# Power.net
KiCad netlist of a schematic drawn in Altium Designer
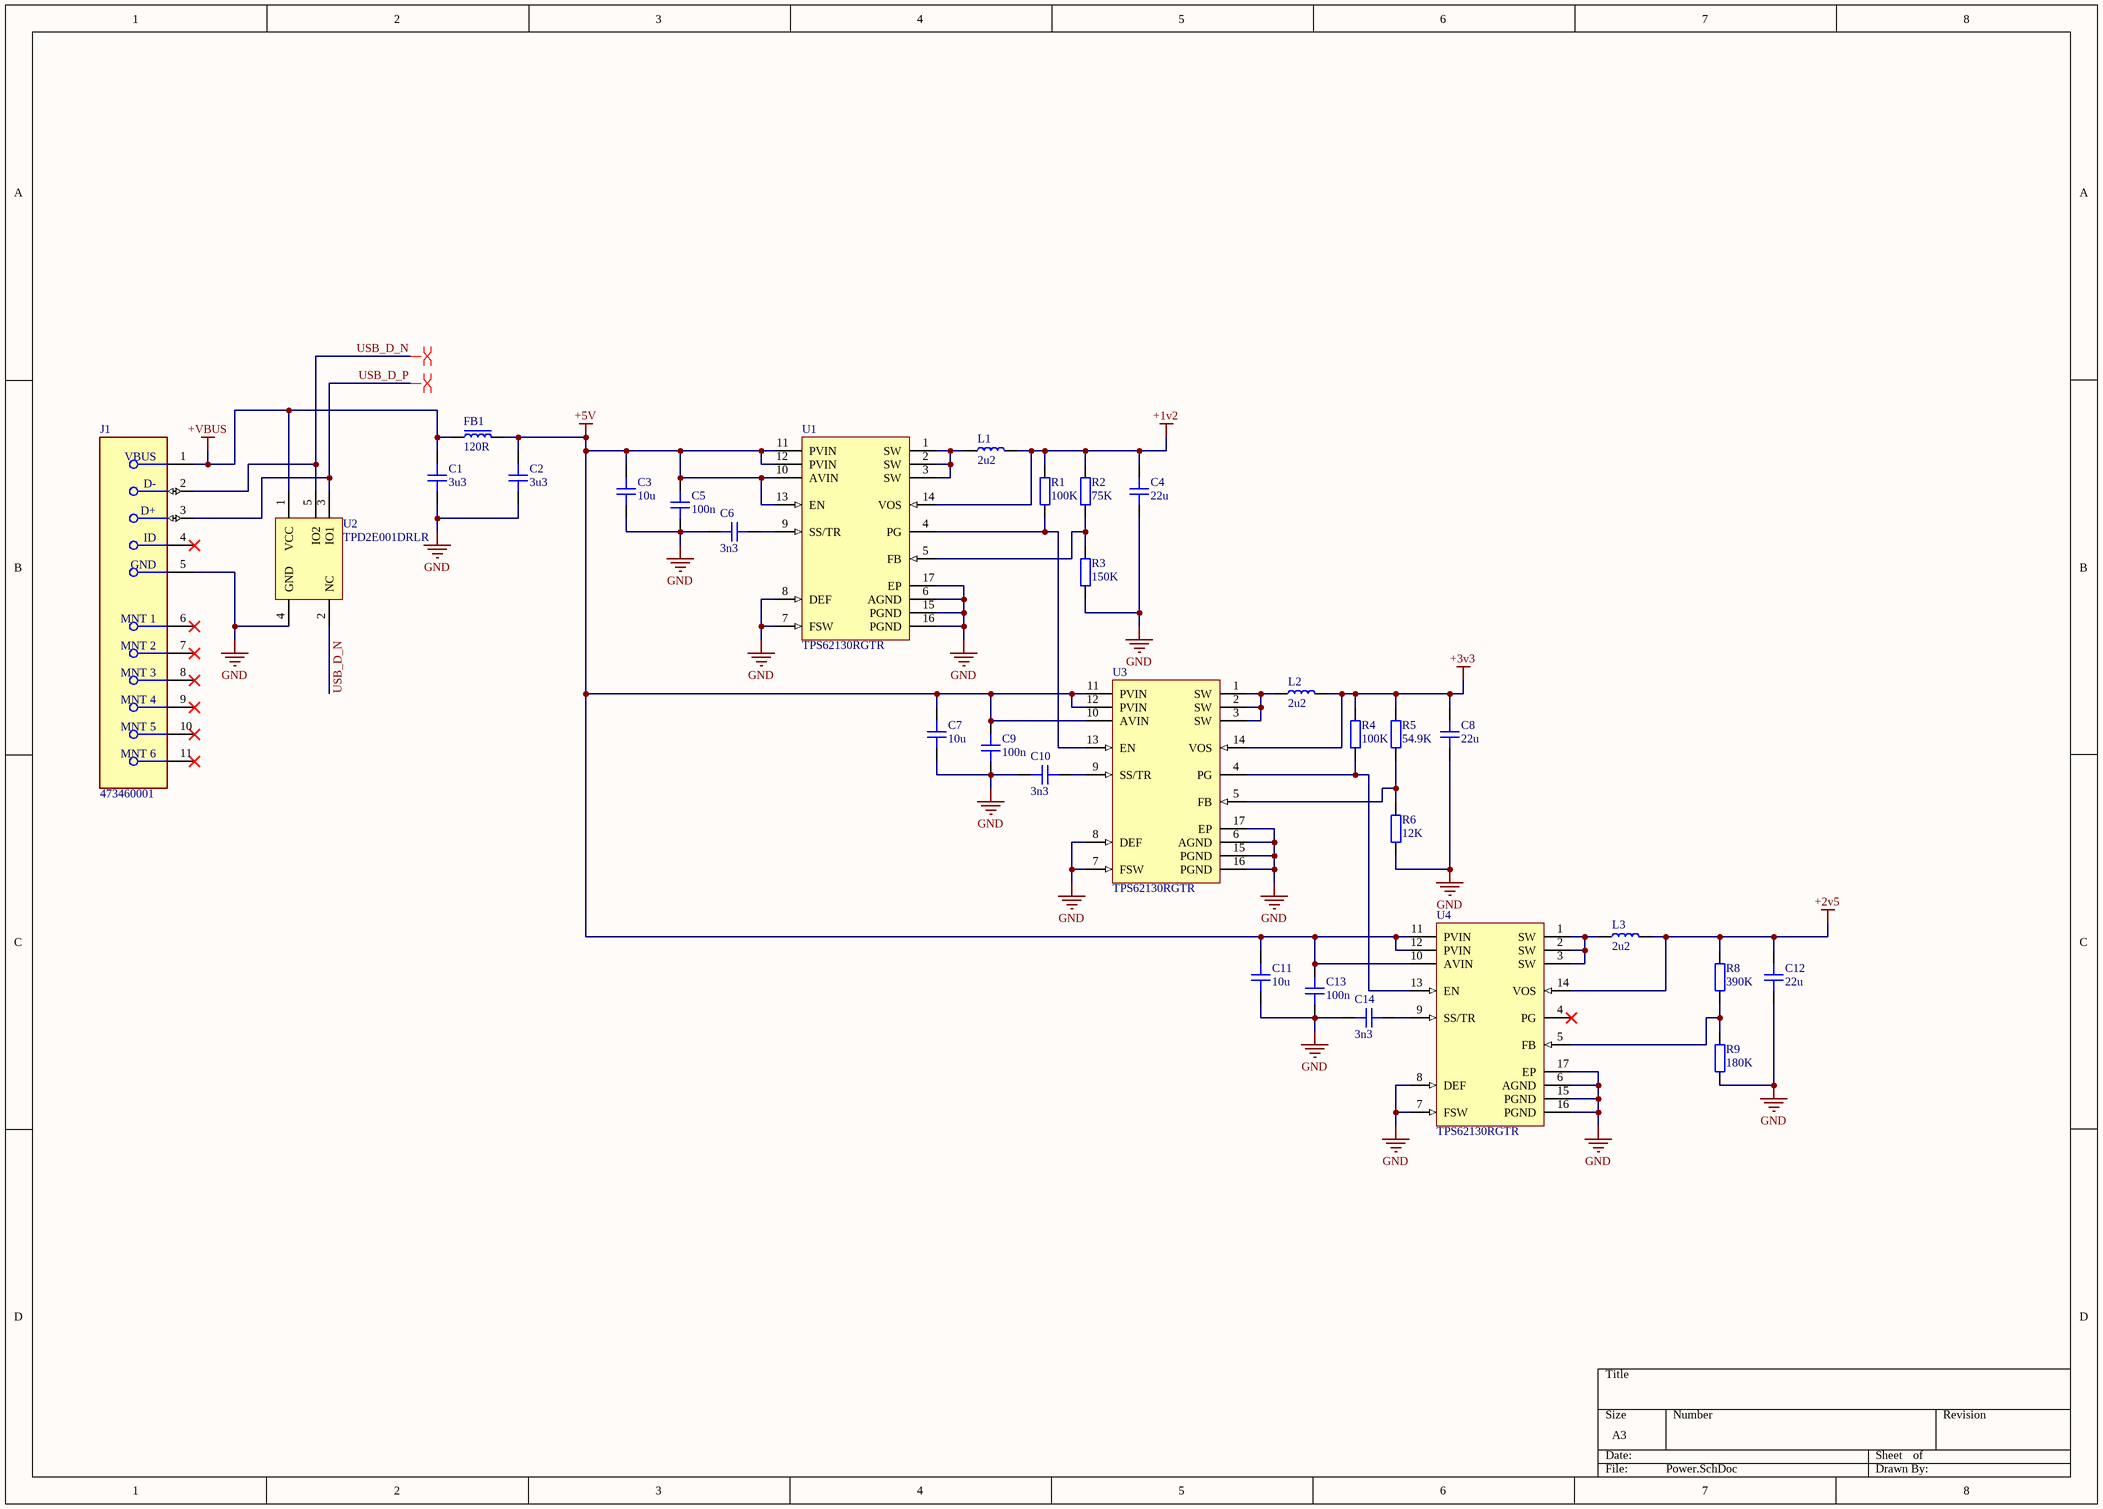
[diagram p0: Power.SchDoc]

(export (version "E")
  (design (tool "Eeschema 10.0.6"))
  (components
    (comp (ref "C1")
      (value "3u3")
      (footprint "CAP_0603")
      (description "Capacitor SMD 0603")
      (fields (field (name "MANUFACTURER PART NUMBER") "TCC0603X5R335M250CT"))
      (libsource (lib "Schematic-Lib-PhilsLab") (part "CAP_0603"))
    )
    (comp (ref "C2")
      (value "3u3")
      (footprint "CAP_0603")
      (description "Capacitor SMD 0603")
      (fields (field (name "MANUFACTURER PART NUMBER") "TCC0603X5R335M250CT"))
      (libsource (lib "Schematic-Lib-PhilsLab") (part "CAP_0603"))
    )
    (comp (ref "C3")
      (value "10u")
      (footprint "CAP_0805")
      (description "Capacitor SMD 0805")
      (fields (field (name "MANUFACTURER PART NUMBER") "CL21B106KOQNNNE"))
      (libsource (lib "Schematic-Lib-PhilsLab") (part "CAP_0805"))
    )
    (comp (ref "C4")
      (value "22u")
      (footprint "CAP_0805")
      (description "Capacitor SMD 0805")
      (fields (field (name "MANUFACTURER PART NUMBER") "GRM21BZ71A226ME15L"))
      (libsource (lib "Schematic-Lib-PhilsLab") (part "CAP_0805"))
    )
    (comp (ref "C5")
      (value "100n")
      (footprint "CAP_0402")
      (description "Capacitor SMD 0402")
      (fields (field (name "MANUFACTURER PART NUMBER") "CL05B104KO5NNNC"))
      (libsource (lib "Schematic-Lib-PhilsLab") (part "CAP_0402"))
    )
    (comp (ref "C6")
      (value "3n3")
      (footprint "CAP_0402")
      (description "Capacitor SMD 0402")
      (fields (field (name "MANUFACTURER PART NUMBER") "CL05B332KB5NNNC"))
      (libsource (lib "Schematic-Lib-PhilsLab") (part "CAP_0402"))
    )
    (comp (ref "C7")
      (value "10u")
      (footprint "CAP_0805")
      (description "Capacitor SMD 0805")
      (fields (field (name "MANUFACTURER PART NUMBER") "CL21B106KOQNNNE"))
      (libsource (lib "Schematic-Lib-PhilsLab") (part "CAP_0805"))
    )
    (comp (ref "C8")
      (value "22u")
      (footprint "CAP_0805")
      (description "Capacitor SMD 0805")
      (fields (field (name "MANUFACTURER PART NUMBER") "GRM21BZ71A226ME15L"))
      (libsource (lib "Schematic-Lib-PhilsLab") (part "CAP_0805"))
    )
    (comp (ref "C9")
      (value "100n")
      (footprint "CAP_0402")
      (description "Capacitor SMD 0402")
      (fields (field (name "MANUFACTURER PART NUMBER") "CL05B104KO5NNNC"))
      (libsource (lib "Schematic-Lib-PhilsLab") (part "CAP_0402"))
    )
    (comp (ref "C10")
      (value "3n3")
      (footprint "CAP_0402")
      (description "Capacitor SMD 0402")
      (fields (field (name "MANUFACTURER PART NUMBER") "CL05B332KB5NNNC"))
      (libsource (lib "Schematic-Lib-PhilsLab") (part "CAP_0402"))
    )
    (comp (ref "C11")
      (value "10u")
      (footprint "CAP_0805")
      (description "Capacitor SMD 0805")
      (fields (field (name "MANUFACTURER PART NUMBER") "CL21B106KOQNNNE"))
      (libsource (lib "Schematic-Lib-PhilsLab") (part "CAP_0805"))
    )
    (comp (ref "C12")
      (value "22u")
      (footprint "CAP_0805")
      (description "Capacitor SMD 0805")
      (fields (field (name "MANUFACTURER PART NUMBER") "GRM21BZ71A226ME15L"))
      (libsource (lib "Schematic-Lib-PhilsLab") (part "CAP_0805"))
    )
    (comp (ref "C13")
      (value "100n")
      (footprint "CAP_0402")
      (description "Capacitor SMD 0402")
      (fields (field (name "MANUFACTURER PART NUMBER") "CL05B104KO5NNNC"))
      (libsource (lib "Schematic-Lib-PhilsLab") (part "CAP_0402"))
    )
    (comp (ref "C14")
      (value "3n3")
      (footprint "CAP_0402")
      (description "Capacitor SMD 0402")
      (fields (field (name "MANUFACTURER PART NUMBER") "CL05B332KB5NNNC"))
      (libsource (lib "Schematic-Lib-PhilsLab") (part "CAP_0402"))
    )
    (comp (ref "FB1")
      (value "120R")
      (footprint "FB_0603")
      (description "Ferrite Bead SMD 0603")
      (fields (field (name "MANUFACTURER PART NUMBER") "BLM18PG121SN1D"))
      (libsource (lib "Schematic-Lib-PhilsLab") (part "FB_0603"))
    )
    (comp (ref "J1")
      (value "473460001")
      (footprint "FP-473460001-MFG")
      (description "CONN RCPT USB2.0 MICRO B SMD R/A")
      (fields
        (field (name "OCTOPART") "https://octopart.com/47346-0001-molex-7164928")
        (field (name "MANUFACTURER") "Molex")
      )
      (libsource (lib "Altium Content Vault") (part "53ae1f1d9b557310b43ca686e5bb76a"))
    )
    (comp (ref "L1")
      (value "2u2")
      (footprint "IND_1008")
      (description "Inductor SMD 1008")
      (fields (field (name "MANUFACTURER PART NUMBER") "LQM2HPN2R2MG0L"))
      (libsource (lib "Schematic-Lib-PhilsLab") (part "IND_1008"))
    )
    (comp (ref "L2")
      (value "2u2")
      (footprint "IND_1008")
      (description "Inductor SMD 1008")
      (fields (field (name "MANUFACTURER PART NUMBER") "LQM2HPN2R2MG0L"))
      (libsource (lib "Schematic-Lib-PhilsLab") (part "IND_1008"))
    )
    (comp (ref "L3")
      (value "2u2")
      (footprint "IND_1008")
      (description "Inductor SMD 1008")
      (fields (field (name "MANUFACTURER PART NUMBER") "LQM2HPN2R2MG0L"))
      (libsource (lib "Schematic-Lib-PhilsLab") (part "IND_1008"))
    )
    (comp (ref "R1")
      (value "100K")
      (footprint "RES_0402")
      (description "Resistor SMD 0402")
      (fields (field (name "MANUFACTURER PART NUMBER") "0402WGF1003TCE"))
      (libsource (lib "Schematic-Lib-PhilsLab") (part "RES_0402"))
    )
    (comp (ref "R2")
      (value "75K")
      (footprint "RES_0402")
      (description "Resistor SMD 0402")
      (fields (field (name "MANUFACTURER PART NUMBER") "0402WGF7502TCE"))
      (libsource (lib "Schematic-Lib-PhilsLab") (part "RES_0402"))
    )
    (comp (ref "R3")
      (value "150K")
      (footprint "RES_0402")
      (description "Resistor SMD 0402")
      (fields (field (name "MANUFACTURER PART NUMBER") "FRC0402F1503TS"))
      (libsource (lib "Schematic-Lib-PhilsLab") (part "RES_0402"))
    )
    (comp (ref "R4")
      (value "100K")
      (footprint "RES_0402")
      (description "Resistor SMD 0402")
      (fields (field (name "MANUFACTURER PART NUMBER") "0402WGF1003TCE"))
      (libsource (lib "Schematic-Lib-PhilsLab") (part "RES_0402"))
    )
    (comp (ref "R5")
      (value "54.9K")
      (footprint "RES_0402")
      (description "Resistor SMD 0402")
      (fields (field (name "MANUFACTURER PART NUMBER") "0402WGF5492TCE"))
      (libsource (lib "Schematic-Lib-PhilsLab") (part "RES_0402"))
    )
    (comp (ref "R6")
      (value "12K")
      (footprint "RES_0402")
      (description "Resistor SMD 0402")
      (fields (field (name "MANUFACTURER PART NUMBER") "0402WGF1202TCE"))
      (libsource (lib "Schematic-Lib-PhilsLab") (part "RES_0402"))
    )
    (comp (ref "R8")
      (value "390K")
      (footprint "RES_0402")
      (description "Resistor SMD 0402")
      (fields (field (name "MANUFACTURER PART NUMBER") "0402WGF3903TCE"))
      (libsource (lib "Schematic-Lib-PhilsLab") (part "RES_0402"))
    )
    (comp (ref "R9")
      (value "180K")
      (footprint "RES_0402")
      (description "Resistor SMD 0402")
      (fields (field (name "MANUFACTURER PART NUMBER") "0402WGF1803TCE"))
      (libsource (lib "Schematic-Lib-PhilsLab") (part "RES_0402"))
    )
    (comp (ref "U1")
      (value "TPS62130RGTR")
      (footprint "RGT0016C_V")
      (fields (field (name "MANUFACTURER") "Texas Instruments"))
      (libsource (lib "Altium Content Vault") (part "TI-TPS62130RGT16-1700X1700TP"))
    )
    (comp (ref "U2")
      (value "TPD2E001DRLR")
      (footprint "DRL0005A_L")
      (fields (field (name "MANUFACTURER") "Texas Instruments"))
      (libsource (lib "Altium Content Vault") (part "TI-TPD2E001-SOT_DRL-5"))
    )
    (comp (ref "U3")
      (value "TPS62130RGTR")
      (footprint "RGT0016C_V")
      (fields (field (name "MANUFACTURER") "Texas Instruments"))
      (libsource (lib "Altium Content Vault") (part "TI-TPS62130RGT16-1700X1700TP"))
    )
    (comp (ref "U4")
      (value "TPS62130RGTR")
      (footprint "RGT0016C_V")
      (fields (field (name "MANUFACTURER") "Texas Instruments"))
      (libsource (lib "Altium Content Vault") (part "TI-TPS62130RGT16-1700X1700TP"))
    )
  )
  (nets
    (net (code "1") (name "+1v2") (class "Default")
      (node (ref "C4") (pin "2") (pinfunction "2_2") (pintype "passive"))
      (node (ref "L1") (pin "2") (pinfunction "2_2") (pintype "passive"))
      (node (ref "R1") (pin "2") (pinfunction "2_2") (pintype "passive"))
      (node (ref "R2") (pin "2") (pinfunction "2_2") (pintype "passive"))
      (node (ref "U1") (pin "14") (pinfunction "VOS_14") (pintype "input"))
    )
    (net (code "2") (name "+2v5") (class "Default")
      (node (ref "C12") (pin "2") (pinfunction "2_2") (pintype "passive"))
      (node (ref "L3") (pin "2") (pinfunction "2_2") (pintype "passive"))
      (node (ref "R8") (pin "2") (pinfunction "2_2") (pintype "passive"))
      (node (ref "U4") (pin "14") (pinfunction "VOS_14") (pintype "input"))
    )
    (net (code "3") (name "+3v3") (class "Default")
      (node (ref "C8") (pin "2") (pinfunction "2_2") (pintype "passive"))
      (node (ref "L2") (pin "2") (pinfunction "2_2") (pintype "passive"))
      (node (ref "R4") (pin "2") (pinfunction "2_2") (pintype "passive"))
      (node (ref "R5") (pin "2") (pinfunction "2_2") (pintype "passive"))
      (node (ref "U3") (pin "14") (pinfunction "VOS_14") (pintype "input"))
    )
    (net (code "4") (name "+5V") (class "Default")
      (node (ref "C11") (pin "2") (pinfunction "2_2") (pintype "passive"))
      (node (ref "C13") (pin "2") (pinfunction "2_2") (pintype "passive"))
      (node (ref "C2") (pin "2") (pinfunction "2_2") (pintype "passive"))
      (node (ref "C3") (pin "2") (pinfunction "2_2") (pintype "passive"))
      (node (ref "C5") (pin "2") (pinfunction "2_2") (pintype "passive"))
      (node (ref "C7") (pin "2") (pinfunction "2_2") (pintype "passive"))
      (node (ref "C9") (pin "2") (pinfunction "2_2") (pintype "passive"))
      (node (ref "FB1") (pin "2") (pinfunction "2_2") (pintype "passive"))
      (node (ref "U1") (pin "10") (pinfunction "AVIN_10") (pintype "power_in"))
      (node (ref "U1") (pin "11") (pinfunction "PVIN_11") (pintype "power_in"))
      (node (ref "U1") (pin "12") (pinfunction "PVIN_12") (pintype "power_in"))
      (node (ref "U1") (pin "13") (pinfunction "EN_13") (pintype "input"))
      (node (ref "U3") (pin "10") (pinfunction "AVIN_10") (pintype "power_in"))
      (node (ref "U3") (pin "11") (pinfunction "PVIN_11") (pintype "power_in"))
      (node (ref "U3") (pin "12") (pinfunction "PVIN_12") (pintype "power_in"))
      (node (ref "U4") (pin "10") (pinfunction "AVIN_10") (pintype "power_in"))
      (node (ref "U4") (pin "11") (pinfunction "PVIN_11") (pintype "power_in"))
      (node (ref "U4") (pin "12") (pinfunction "PVIN_12") (pintype "power_in"))
    )
    (net (code "5") (name "+VBUS") (class "Default")
      (node (ref "C1") (pin "2") (pinfunction "2_2") (pintype "passive"))
      (node (ref "FB1") (pin "1") (pinfunction "1_1") (pintype "passive"))
      (node (ref "J1") (pin "1") (pinfunction "VBUS_1") (pintype "power_in"))
      (node (ref "U2") (pin "1") (pinfunction "VCC_1") (pintype "power_in"))
    )
    (net (code "6") (name "/USB_D_N") (class "Default")
      (node (ref "J1") (pin "2") (pinfunction "D-_2") (pintype "bidirectional"))
      (node (ref "U2") (pin "2") (pinfunction "NC_2") (pintype "passive"))
      (node (ref "U2") (pin "5") (pinfunction "IO2_5") (pintype "passive"))
    )
    (net (code "7") (name "/USB_D_P") (class "Default")
      (node (ref "J1") (pin "3") (pinfunction "D+_3") (pintype "bidirectional"))
      (node (ref "U2") (pin "3") (pinfunction "IO1_3") (pintype "passive"))
    )
    (net (code "8") (name "GND") (class "Default")
      (node (ref "C1") (pin "1") (pinfunction "1_1") (pintype "passive"))
      (node (ref "C10") (pin "2") (pinfunction "2_2") (pintype "passive"))
      (node (ref "C11") (pin "1") (pinfunction "1_1") (pintype "passive"))
      (node (ref "C12") (pin "1") (pinfunction "1_1") (pintype "passive"))
      (node (ref "C13") (pin "1") (pinfunction "1_1") (pintype "passive"))
      (node (ref "C14") (pin "2") (pinfunction "2_2") (pintype "passive"))
      (node (ref "C2") (pin "1") (pinfunction "1_1") (pintype "passive"))
      (node (ref "C3") (pin "1") (pinfunction "1_1") (pintype "passive"))
      (node (ref "C4") (pin "1") (pinfunction "1_1") (pintype "passive"))
      (node (ref "C5") (pin "1") (pinfunction "1_1") (pintype "passive"))
      (node (ref "C6") (pin "2") (pinfunction "2_2") (pintype "passive"))
      (node (ref "C7") (pin "1") (pinfunction "1_1") (pintype "passive"))
      (node (ref "C8") (pin "1") (pinfunction "1_1") (pintype "passive"))
      (node (ref "C9") (pin "1") (pinfunction "1_1") (pintype "passive"))
      (node (ref "J1") (pin "5") (pinfunction "GND_5") (pintype "power_in"))
      (node (ref "R3") (pin "1") (pinfunction "1_1") (pintype "passive"))
      (node (ref "R6") (pin "1") (pinfunction "1_1") (pintype "passive"))
      (node (ref "R9") (pin "1") (pinfunction "1_1") (pintype "passive"))
      (node (ref "U1") (pin "15") (pinfunction "PGND_15") (pintype "power_in"))
      (node (ref "U1") (pin "16") (pinfunction "PGND_16") (pintype "power_in"))
      (node (ref "U1") (pin "17") (pinfunction "EP_17") (pintype "power_in"))
      (node (ref "U1") (pin "6") (pinfunction "AGND_6") (pintype "power_in"))
      (node (ref "U1") (pin "7") (pinfunction "FSW_7") (pintype "input"))
      (node (ref "U1") (pin "8") (pinfunction "DEF_8") (pintype "input"))
      (node (ref "U2") (pin "4") (pinfunction "GND_4") (pintype "power_in"))
      (node (ref "U3") (pin "15") (pinfunction "PGND_15") (pintype "power_in"))
      (node (ref "U3") (pin "16") (pinfunction "PGND_16") (pintype "power_in"))
      (node (ref "U3") (pin "17") (pinfunction "EP_17") (pintype "power_in"))
      (node (ref "U3") (pin "6") (pinfunction "AGND_6") (pintype "power_in"))
      (node (ref "U3") (pin "7") (pinfunction "FSW_7") (pintype "input"))
      (node (ref "U3") (pin "8") (pinfunction "DEF_8") (pintype "input"))
      (node (ref "U4") (pin "15") (pinfunction "PGND_15") (pintype "power_in"))
      (node (ref "U4") (pin "16") (pinfunction "PGND_16") (pintype "power_in"))
      (node (ref "U4") (pin "17") (pinfunction "EP_17") (pintype "power_in"))
      (node (ref "U4") (pin "6") (pinfunction "AGND_6") (pintype "power_in"))
      (node (ref "U4") (pin "7") (pinfunction "FSW_7") (pintype "input"))
      (node (ref "U4") (pin "8") (pinfunction "DEF_8") (pintype "input"))
    )
    (net (code "9") (name "Net-(L1-Pad1)") (class "Default")
      (node (ref "L1") (pin "1") (pinfunction "1_1") (pintype "passive"))
      (node (ref "U1") (pin "1") (pinfunction "SW_1") (pintype "power_in"))
      (node (ref "U1") (pin "2") (pinfunction "SW_2") (pintype "power_in"))
      (node (ref "U1") (pin "3") (pinfunction "SW_3") (pintype "power_in"))
    )
    (net (code "10") (name "Net-(L2-Pad1)") (class "Default")
      (node (ref "L2") (pin "1") (pinfunction "1_1") (pintype "passive"))
      (node (ref "U3") (pin "1") (pinfunction "SW_1") (pintype "power_in"))
      (node (ref "U3") (pin "2") (pinfunction "SW_2") (pintype "power_in"))
      (node (ref "U3") (pin "3") (pinfunction "SW_3") (pintype "power_in"))
    )
    (net (code "11") (name "Net-(L3-Pad1)") (class "Default")
      (node (ref "L3") (pin "1") (pinfunction "1_1") (pintype "passive"))
      (node (ref "U4") (pin "1") (pinfunction "SW_1") (pintype "power_in"))
      (node (ref "U4") (pin "2") (pinfunction "SW_2") (pintype "power_in"))
      (node (ref "U4") (pin "3") (pinfunction "SW_3") (pintype "power_in"))
    )
    (net (code "12") (name "Net-(U1-FB)") (class "Default")
      (node (ref "R2") (pin "1") (pinfunction "1_1") (pintype "passive"))
      (node (ref "R3") (pin "2") (pinfunction "2_2") (pintype "passive"))
      (node (ref "U1") (pin "5") (pinfunction "FB_5") (pintype "input"))
    )
    (net (code "13") (name "Net-(U1-PG)") (class "Default")
      (node (ref "R1") (pin "1") (pinfunction "1_1") (pintype "passive"))
      (node (ref "U1") (pin "4") (pinfunction "PG_4") (pintype "tri_state"))
      (node (ref "U3") (pin "13") (pinfunction "EN_13") (pintype "input"))
    )
    (net (code "14") (name "Net-(U1-SS{slash}TR)") (class "Default")
      (node (ref "C6") (pin "1") (pinfunction "1_1") (pintype "passive"))
      (node (ref "U1") (pin "9") (pinfunction "SS/TR_9") (pintype "input"))
    )
    (net (code "15") (name "Net-(U3-FB)") (class "Default")
      (node (ref "R5") (pin "1") (pinfunction "1_1") (pintype "passive"))
      (node (ref "R6") (pin "2") (pinfunction "2_2") (pintype "passive"))
      (node (ref "U3") (pin "5") (pinfunction "FB_5") (pintype "input"))
    )
    (net (code "16") (name "Net-(U3-PG)") (class "Default")
      (node (ref "R4") (pin "1") (pinfunction "1_1") (pintype "passive"))
      (node (ref "U3") (pin "4") (pinfunction "PG_4") (pintype "tri_state"))
      (node (ref "U4") (pin "13") (pinfunction "EN_13") (pintype "input"))
    )
    (net (code "17") (name "Net-(U3-SS{slash}TR)") (class "Default")
      (node (ref "C10") (pin "1") (pinfunction "1_1") (pintype "passive"))
      (node (ref "U3") (pin "9") (pinfunction "SS/TR_9") (pintype "input"))
    )
    (net (code "18") (name "Net-(U4-FB)") (class "Default")
      (node (ref "R8") (pin "1") (pinfunction "1_1") (pintype "passive"))
      (node (ref "R9") (pin "2") (pinfunction "2_2") (pintype "passive"))
      (node (ref "U4") (pin "5") (pinfunction "FB_5") (pintype "input"))
    )
    (net (code "19") (name "Net-(U4-SS{slash}TR)") (class "Default")
      (node (ref "C14") (pin "1") (pinfunction "1_1") (pintype "passive"))
      (node (ref "U4") (pin "9") (pinfunction "SS/TR_9") (pintype "input"))
    )
    (net (code "20") (name "unconnected-(J1-ID-Pad4)") (class "Default")
      (node (ref "J1") (pin "4") (pinfunction "ID_4") (pintype "passive+no_connect"))
    )
    (net (code "21") (name "unconnected-(J1-MNT_1-Pad6)") (class "Default")
      (node (ref "J1") (pin "6") (pinfunction "MNT_1_6") (pintype "passive+no_connect"))
    )
    (net (code "22") (name "unconnected-(J1-MNT_2-Pad7)") (class "Default")
      (node (ref "J1") (pin "7") (pinfunction "MNT_2_7") (pintype "passive+no_connect"))
    )
    (net (code "23") (name "unconnected-(J1-MNT_3-Pad8)") (class "Default")
      (node (ref "J1") (pin "8") (pinfunction "MNT_3_8") (pintype "passive+no_connect"))
    )
    (net (code "24") (name "unconnected-(J1-MNT_4-Pad9)") (class "Default")
      (node (ref "J1") (pin "9") (pinfunction "MNT_4_9") (pintype "passive+no_connect"))
    )
    (net (code "25") (name "unconnected-(J1-MNT_5-Pad10)") (class "Default")
      (node (ref "J1") (pin "10") (pinfunction "MNT_5_10") (pintype "passive+no_connect"))
    )
    (net (code "26") (name "unconnected-(J1-MNT_6-Pad11)") (class "Default")
      (node (ref "J1") (pin "11") (pinfunction "MNT_6_11") (pintype "passive+no_connect"))
    )
    (net (code "27") (name "unconnected-(U4-PG-Pad4)") (class "Default")
      (node (ref "U4") (pin "4") (pinfunction "PG_4") (pintype "tri_state+no_connect"))
    )
  )
)
